# SRX-dataport-interceptor-breakout.net
KiCad netlist of a schematic drawn in EAGLE
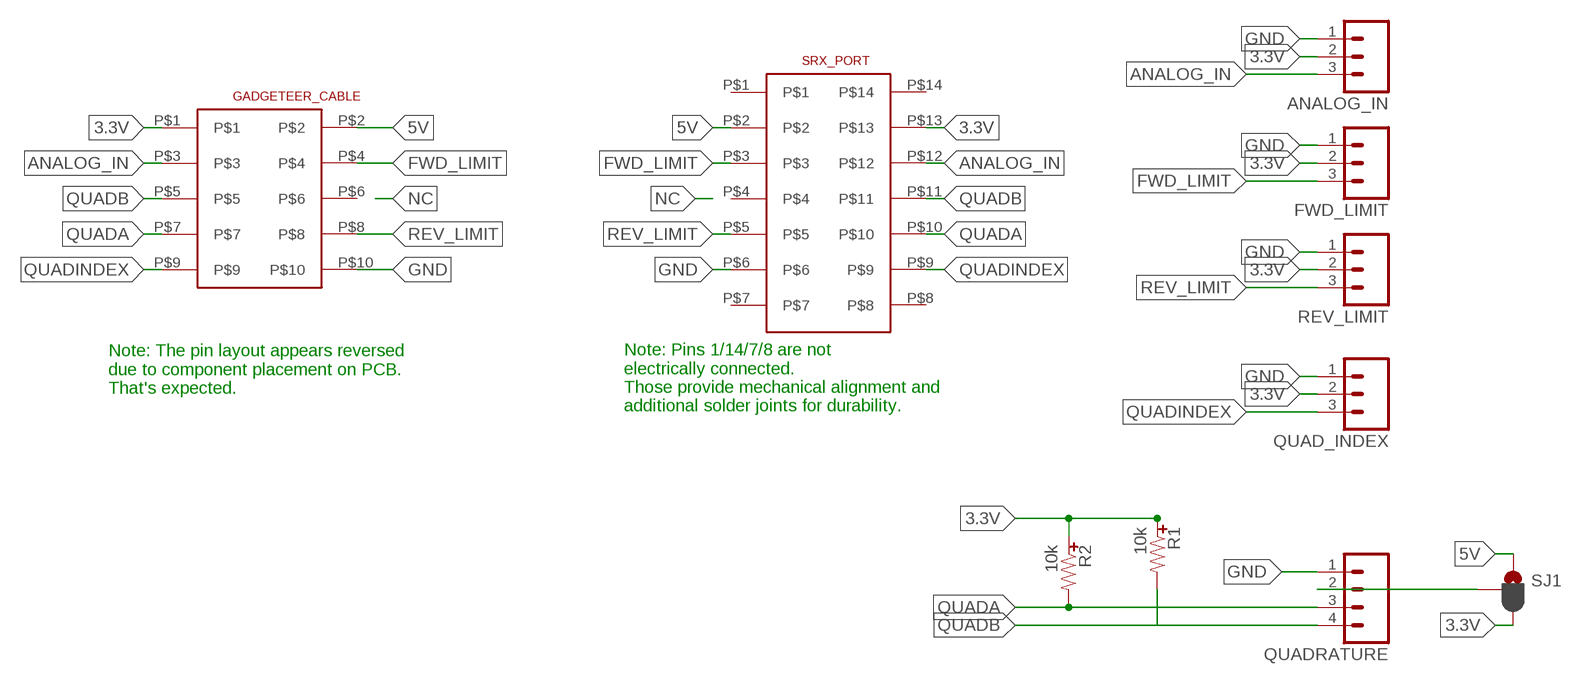
[diagram p0: schematic, sheet 1]

(export (version "E")
  (design (tool "Eeschema 10.0.6"))
  (components
    (comp (ref "ANALOG_IN")
      (value "M03LOCK")
      (footprint "eagle-import:1X03_LOCK")
      (libsource (lib "eagle-import") (part "M03LOCK"))
    )
    (comp (ref "FWD_LIMIT")
      (value "M03LOCK")
      (footprint "eagle-import:1X03_LOCK")
      (libsource (lib "eagle-import") (part "M03LOCK"))
    )
    (comp (ref "GADGETEER_CABLE")
      (value "M05X02M_SHROUDED")
      (footprint "eagle-import:M2X05_M_SHROUDED")
      (libsource (lib "eagle-import") (part "M05X02M_SHROUDED"))
    )
    (comp (ref "QUADRATURE")
      (value "M04LOCK")
      (footprint "eagle-import:1X04_LOCK")
      (libsource (lib "eagle-import") (part "M04LOCK"))
    )
    (comp (ref "QUAD_INDEX")
      (value "M03LOCK")
      (footprint "eagle-import:1X03_LOCK")
      (libsource (lib "eagle-import") (part "M03LOCK"))
    )
    (comp (ref "R1")
      (value "10k")
      (footprint "eagle-import:0402-0603-0805-UNIVERSAL")
      (libsource (lib "eagle-import") (part "RESISTORUNIVERSAL"))
    )
    (comp (ref "R2")
      (value "10k")
      (footprint "eagle-import:0402-0603-0805-UNIVERSAL")
      (libsource (lib "eagle-import") (part "RESISTORUNIVERSAL"))
    )
    (comp (ref "REV_LIMIT")
      (value "M03LOCK")
      (footprint "eagle-import:1X03_LOCK")
      (libsource (lib "eagle-import") (part "M03LOCK"))
    )
    (comp (ref "SJ1")
      (value "JUMPER-PAD-3-2OF3_NC_BY_PASTE")
      (footprint "eagle-import:PAD-JUMPER-3-2OF3_NC_BY_PASTE_YES_SILK_FULL_BOX")
      (libsource (lib "eagle-import") (part "JUMPER-PAD-3-2OF3_NC_BY_PASTE"))
    )
    (comp (ref "SRX_PORT")
      (value "M07X0220021321-00014TFLF")
      (footprint "eagle-import:M2X07_SMD")
      (libsource (lib "eagle-import") (part "M07X0220021321-00014TFLF"))
    )
  )
  (nets
    (net (code "1") (name "3.3V") (class "Default")
      (node (ref "ANALOG_IN") (pin "2") (pinfunction "2_2") (pintype "passive"))
      (node (ref "FWD_LIMIT") (pin "2") (pinfunction "2_2") (pintype "passive"))
      (node (ref "GADGETEER_CABLE") (pin "P$1") (pinfunction "P$1_P$1") (pintype "bidirectional"))
      (node (ref "QUAD_INDEX") (pin "2") (pinfunction "2_2") (pintype "passive"))
      (node (ref "R1") (pin "+") (pinfunction "1_+") (pintype "passive"))
      (node (ref "R2") (pin "+") (pinfunction "1_+") (pintype "passive"))
      (node (ref "REV_LIMIT") (pin "2") (pinfunction "2_2") (pintype "passive"))
      (node (ref "SJ1") (pin "3") (pinfunction "3_3") (pintype "passive"))
      (node (ref "SRX_PORT") (pin "P$13") (pinfunction "P$13_P$13") (pintype "bidirectional"))
    )
    (net (code "2") (name "5V") (class "Default")
      (node (ref "GADGETEER_CABLE") (pin "P$2") (pinfunction "P$2_P$2") (pintype "bidirectional"))
      (node (ref "SJ1") (pin "1") (pinfunction "1_1") (pintype "passive"))
      (node (ref "SRX_PORT") (pin "P$2") (pinfunction "P$2_P$2") (pintype "bidirectional"))
    )
    (net (code "3") (name "ANALOG_IN") (class "Default")
      (node (ref "ANALOG_IN") (pin "3") (pinfunction "3_3") (pintype "passive"))
      (node (ref "GADGETEER_CABLE") (pin "P$3") (pinfunction "P$3_P$3") (pintype "bidirectional"))
      (node (ref "SRX_PORT") (pin "P$12") (pinfunction "P$12_P$12") (pintype "bidirectional"))
    )
    (net (code "4") (name "FWD_LIMIT") (class "Default")
      (node (ref "FWD_LIMIT") (pin "3") (pinfunction "3_3") (pintype "passive"))
      (node (ref "GADGETEER_CABLE") (pin "P$4") (pinfunction "P$4_P$4") (pintype "bidirectional"))
      (node (ref "SRX_PORT") (pin "P$3") (pinfunction "P$3_P$3") (pintype "bidirectional"))
    )
    (net (code "5") (name "GND") (class "Default")
      (node (ref "ANALOG_IN") (pin "1") (pinfunction "1_1") (pintype "passive"))
      (node (ref "FWD_LIMIT") (pin "1") (pinfunction "1_1") (pintype "passive"))
      (node (ref "GADGETEER_CABLE") (pin "P$10") (pinfunction "P$10_P$10") (pintype "bidirectional"))
      (node (ref "QUADRATURE") (pin "1") (pinfunction "1_1") (pintype "passive"))
      (node (ref "QUAD_INDEX") (pin "1") (pinfunction "1_1") (pintype "passive"))
      (node (ref "REV_LIMIT") (pin "1") (pinfunction "1_1") (pintype "passive"))
      (node (ref "SRX_PORT") (pin "P$6") (pinfunction "P$6_P$6") (pintype "bidirectional"))
    )
    (net (code "7") (name "Net-(QUADRATURE-Pad2)") (class "Default")
      (node (ref "QUADRATURE") (pin "2") (pinfunction "2_2") (pintype "passive"))
      (node (ref "SJ1") (pin "2") (pinfunction "2_2") (pintype "passive"))
    )
    (net (code "8") (name "QUADA") (class "Default")
      (node (ref "GADGETEER_CABLE") (pin "P$7") (pinfunction "P$7_P$7") (pintype "bidirectional"))
      (node (ref "QUADRATURE") (pin "3") (pinfunction "3_3") (pintype "passive"))
      (node (ref "R2") (pin "-") (pinfunction "2_-") (pintype "passive"))
      (node (ref "SRX_PORT") (pin "P$10") (pinfunction "P$10_P$10") (pintype "bidirectional"))
    )
    (net (code "9") (name "QUADB") (class "Default")
      (node (ref "GADGETEER_CABLE") (pin "P$5") (pinfunction "P$5_P$5") (pintype "bidirectional"))
      (node (ref "QUADRATURE") (pin "4") (pinfunction "4_4") (pintype "passive"))
      (node (ref "R1") (pin "-") (pinfunction "2_-") (pintype "passive"))
      (node (ref "SRX_PORT") (pin "P$11") (pinfunction "P$11_P$11") (pintype "bidirectional"))
    )
    (net (code "10") (name "QUADINDEX") (class "Default")
      (node (ref "GADGETEER_CABLE") (pin "P$9") (pinfunction "P$9_P$9") (pintype "bidirectional"))
      (node (ref "QUAD_INDEX") (pin "3") (pinfunction "3_3") (pintype "passive"))
      (node (ref "SRX_PORT") (pin "P$9") (pinfunction "P$9_P$9") (pintype "bidirectional"))
    )
    (net (code "11") (name "REV_LIMIT") (class "Default")
      (node (ref "GADGETEER_CABLE") (pin "P$8") (pinfunction "P$8_P$8") (pintype "bidirectional"))
      (node (ref "REV_LIMIT") (pin "3") (pinfunction "3_3") (pintype "passive"))
      (node (ref "SRX_PORT") (pin "P$5") (pinfunction "P$5_P$5") (pintype "bidirectional"))
    )
    (net (code "12") (name "unconnected-(GADGETEER_CABLE-PadP$6)") (class "Default")
      (node (ref "GADGETEER_CABLE") (pin "P$6") (pinfunction "P$6_P$6") (pintype "bidirectional"))
    )
    (net (code "13") (name "unconnected-(SRX_PORT-PadP$1)") (class "Default")
      (node (ref "SRX_PORT") (pin "P$1") (pinfunction "P$1_P$1") (pintype "bidirectional"))
    )
    (net (code "14") (name "unconnected-(SRX_PORT-PadP$4)") (class "Default")
      (node (ref "SRX_PORT") (pin "P$4") (pinfunction "P$4_P$4") (pintype "bidirectional"))
    )
    (net (code "15") (name "unconnected-(SRX_PORT-PadP$7)") (class "Default")
      (node (ref "SRX_PORT") (pin "P$7") (pinfunction "P$7_P$7") (pintype "bidirectional"))
    )
    (net (code "16") (name "unconnected-(SRX_PORT-PadP$8)") (class "Default")
      (node (ref "SRX_PORT") (pin "P$8") (pinfunction "P$8_P$8") (pintype "bidirectional"))
    )
    (net (code "17") (name "unconnected-(SRX_PORT-PadP$14)") (class "Default")
      (node (ref "SRX_PORT") (pin "P$14") (pinfunction "P$14_P$14") (pintype "bidirectional"))
    )
  )
)
